# receiver.net
KiCad netlist of a schematic drawn in EAGLE
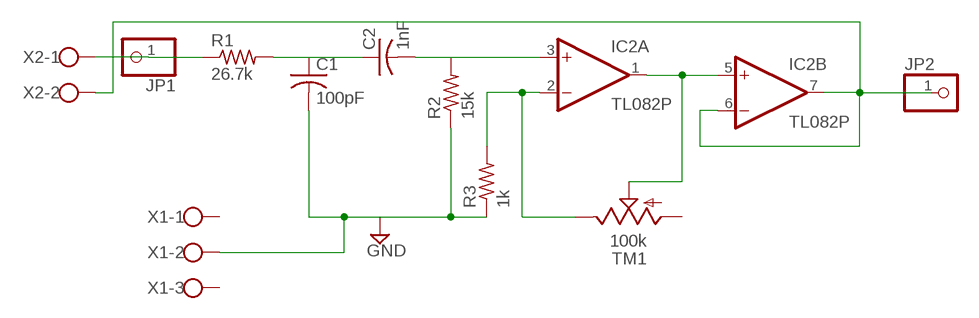
[diagram p0: schematic, sheet 1]

(export (version "E")
  (design (tool "Eeschema 10.0.6"))
  (components
    (comp (ref "C1")
      (value "100pF")
      (footprint "eagle-import:C050-045X075")
      (libsource (lib "eagle-import") (part "C-US050-045X075"))
    )
    (comp (ref "C2")
      (value "1nF")
      (footprint "eagle-import:C050-045X075")
      (libsource (lib "eagle-import") (part "C-US050-045X075"))
    )
    (comp (ref "IC2")
      (value "TL082P")
      (footprint "eagle-import:DIL08")
      (libsource (lib "eagle-import") (part "TL082P"))
    )
    (comp (ref "JP1")
      (value "PINHD-1X1CB")
      (footprint "eagle-import:1X01-CLEANBIG")
      (libsource (lib "eagle-import") (part "PINHD-1X1CB"))
    )
    (comp (ref "JP2")
      (value "PINHD-1X1CB")
      (footprint "eagle-import:1X01-CLEANBIG")
      (libsource (lib "eagle-import") (part "PINHD-1X1CB"))
    )
    (comp (ref "R1")
      (value "26.7k")
      (footprint "eagle-import:0309_10")
      (libsource (lib "eagle-import") (part "R-US_0309/10"))
    )
    (comp (ref "R2")
      (value "15k")
      (footprint "eagle-import:0309_10")
      (libsource (lib "eagle-import") (part "R-US_0309/10"))
    )
    (comp (ref "R3")
      (value "1k")
      (footprint "eagle-import:0309_10")
      (libsource (lib "eagle-import") (part "R-US_0309/10"))
    )
    (comp (ref "TM1")
      (value "100k")
      (footprint "eagle-import:6MM")
      (libsource (lib "eagle-import") (part "TRIM"))
    )
    (comp (ref "X1")
      (value "W237-103")
      (footprint "eagle-import:W237-103")
      (fields (field (name "MPN") "237-103"))
      (libsource (lib "eagle-import") (part "W237-103"))
    )
    (comp (ref "X2")
      (value "W237-102")
      (footprint "eagle-import:W237-102")
      (fields (field (name "MPN") "237-102"))
      (libsource (lib "eagle-import") (part "W237-102"))
    )
  )
  (nets
    (net (code "1") (name "GND") (class "Default")
      (node (ref "C1") (pin "2") (pinfunction "2_2") (pintype "passive"))
      (node (ref "R2") (pin "1") (pinfunction "1_1") (pintype "passive"))
      (node (ref "R3") (pin "1") (pinfunction "1_1") (pintype "passive"))
      (node (ref "X1") (pin "2") (pinfunction "KL_2") (pintype "passive"))
    )
    (net (code "2") (name "Net-(C1-Pad1)") (class "Default")
      (node (ref "C1") (pin "1") (pinfunction "1_1") (pintype "passive"))
      (node (ref "C2") (pin "1") (pinfunction "1_1") (pintype "passive"))
      (node (ref "R1") (pin "2") (pinfunction "2_2") (pintype "passive"))
    )
    (net (code "3") (name "Net-(IC2A-+IN)") (class "Default")
      (node (ref "C2") (pin "2") (pinfunction "2_2") (pintype "passive"))
      (node (ref "IC2") (pin "3") (pinfunction "+IN_3") (pintype "input"))
      (node (ref "R2") (pin "2") (pinfunction "2_2") (pintype "passive"))
    )
    (net (code "4") (name "Net-(IC2A--IN)") (class "Default")
      (node (ref "IC2") (pin "2") (pinfunction "-IN_2") (pintype "input"))
      (node (ref "R3") (pin "2") (pinfunction "2_2") (pintype "passive"))
      (node (ref "TM1") (pin "E") (pinfunction "E_E") (pintype "passive"))
    )
    (net (code "5") (name "Net-(IC2A-OUT)") (class "Default")
      (node (ref "IC2") (pin "1") (pinfunction "OUT_1") (pintype "output"))
      (node (ref "IC2") (pin "5") (pinfunction "+IN_5") (pintype "input"))
      (node (ref "TM1") (pin "S") (pinfunction "S_S") (pintype "passive"))
    )
    (net (code "6") (name "Net-(IC2B--IN)") (class "Default")
      (node (ref "IC2") (pin "6") (pinfunction "-IN_6") (pintype "input"))
      (node (ref "IC2") (pin "7") (pinfunction "OUT_7") (pintype "output"))
      (node (ref "JP2") (pin "1") (pinfunction "1_1") (pintype "passive"))
      (node (ref "X2") (pin "2") (pinfunction "KL_2") (pintype "passive"))
    )
    (net (code "7") (name "Net-(X2A-KL)") (class "Default")
      (node (ref "JP1") (pin "1") (pinfunction "1_1") (pintype "passive"))
      (node (ref "R1") (pin "1") (pinfunction "1_1") (pintype "passive"))
      (node (ref "X2") (pin "1") (pinfunction "KL_1") (pintype "passive"))
    )
    (net (code "8") (name "unconnected-(TM1-PadA)") (class "Default")
      (node (ref "TM1") (pin "A") (pinfunction "A_A") (pintype "passive"))
    )
    (net (code "9") (name "unconnected-(X1A-KL-Pad1)") (class "Default")
      (node (ref "X1") (pin "1") (pinfunction "KL_1") (pintype "passive"))
    )
    (net (code "10") (name "unconnected-(X1C-KL-Pad3)") (class "Default")
      (node (ref "X1") (pin "3") (pinfunction "KL_3") (pintype "passive"))
    )
  )
)
